# FAT44_1.net
KiCad netlist of a schematic drawn in Altium Designer
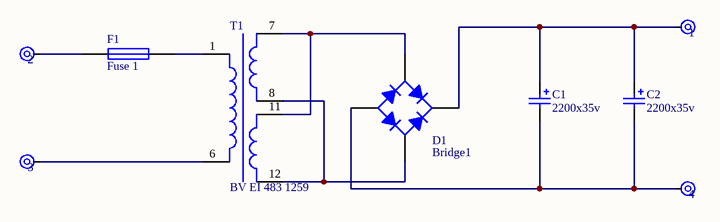
[diagram p0: FAT44_1.SchDoc]

(export (version "E")
  (design (tool "Eeschema 10.0.6"))
  (components
    (comp (ref "1")
      (value "Socket_Ring")
      (footprint "PIN1")
      (description "Socket")
      (fields (field (name "MANUFACTURER") "Generic Components") (field (name "PUBLISHER") "Altium Limited"))
      (libsource (lib "") (part "Socket_Ring_1"))
    )
    (comp (ref "2")
      (value "Socket_Ring")
      (footprint "PIN1")
      (description "Socket")
      (fields (field (name "MANUFACTURER") "Generic Components") (field (name "PUBLISHER") "Altium Limited"))
      (libsource (lib "PAL") (part "Socket_Ring"))
    )
    (comp (ref "3")
      (value "Socket_Ring")
      (footprint "PIN1")
      (description "Socket")
      (fields (field (name "MANUFACTURER") "Generic Components") (field (name "PUBLISHER") "Altium Limited"))
      (libsource (lib "PAL") (part "Socket_Ring"))
    )
    (comp (ref "4")
      (value "Socket_Ring")
      (footprint "PIN1")
      (description "Socket")
      (fields (field (name "MANUFACTURER") "Generic Components") (field (name "PUBLISHER") "Altium Limited"))
      (libsource (lib "") (part "Socket_Ring_1"))
    )
    (comp (ref "C1")
      (value "2200x35v")
      (footprint "el8")
      (description "Polarized Capacitor (Radial)")
      (fields (field (name "MANUFACTURER") "Generic Components") (field (name "PUBLISHER") "Altium Limited"))
      (libsource (lib "BUF") (part "Cap Pol1"))
    )
    (comp (ref "C2")
      (value "2200x35v")
      (footprint "el8")
      (description "Polarized Capacitor (Radial)")
      (fields (field (name "MANUFACTURER") "Generic Components") (field (name "PUBLISHER") "Altium Limited"))
      (libsource (lib "BUF") (part "Cap Pol1"))
    )
    (comp (ref "D1")
      (value "Bridge1")
      (footprint "GSIB2580")
      (description "Full Wave Diode Bridge")
      (fields (field (name "MANUFACTURER") "Generic Components") (field (name "PUBLISHER") "Altium Limited"))
      (libsource (lib "Miscellaneous Devices") (part "Bridge1"))
    )
    (comp (ref "F1")
      (value "Fuse 1")
      (footprint "FUSE3")
      (description "Fuse")
      (fields (field (name "MANUFACTURER") "Generic Components") (field (name "PUBLISHER") "Altium Limited"))
      (libsource (lib "Miscellaneous Devices") (part "Fuse 1"))
    )
    (comp (ref "T1")
      (value "BV EI 483 1259")
      (footprint "BV EI 483 1259_LUT")
      (fields (field (name "MANUFACTURER") "Generic Components") (field (name "PUBLISHER") "Altium Limited"))
      (libsource (lib "PAL") (part "BV EI 483 1259"))
    )
  )
  (nets
    (net (code "1") (name "Net-(2-Pad1)") (class "Default")
      (node (ref "2") (pin "1") (pinfunction "1_1") (pintype "passive"))
      (node (ref "F1") (pin "1") (pinfunction "1_1") (pintype "passive"))
    )
    (net (code "2") (name "Net-(D1-A)") (class "Default")
      (node (ref "4") (pin "1") (pinfunction "1_1") (pintype "passive"))
      (node (ref "C1") (pin "2") (pinfunction "2_2") (pintype "passive"))
      (node (ref "C2") (pin "2") (pinfunction "2_2") (pintype "passive"))
      (node (ref "D1") (pin "1") (pinfunction "A_1") (pintype "passive"))
    )
    (net (code "3") (name "Net-(D1-C-Pad2)") (class "Default")
      (node (ref "D1") (pin "2") (pinfunction "C_2") (pintype "passive"))
      (node (ref "T1") (pin "11") (pinfunction "Sec1+_11") (pintype "passive"))
      (node (ref "T1") (pin "7") (pinfunction "Sec1+_7") (pintype "passive"))
    )
    (net (code "4") (name "Net-(D1-C-Pad4)") (class "Default")
      (node (ref "D1") (pin "4") (pinfunction "C_4") (pintype "passive"))
      (node (ref "T1") (pin "12") (pinfunction "Sec1-_12") (pintype "passive"))
      (node (ref "T1") (pin "8") (pinfunction "Sec1-_8") (pintype "passive"))
    )
    (net (code "5") (name "Net-(D1-K)") (class "Default")
      (node (ref "1") (pin "1") (pinfunction "1_1") (pintype "passive"))
      (node (ref "C1") (pin "1") (pinfunction "1_1") (pintype "passive"))
      (node (ref "C2") (pin "1") (pinfunction "1_1") (pintype "passive"))
      (node (ref "D1") (pin "3") (pinfunction "K_3") (pintype "passive"))
    )
    (net (code "6") (name "Net-(T1-Pri+)") (class "Default")
      (node (ref "F1") (pin "2") (pinfunction "2_2") (pintype "passive"))
      (node (ref "T1") (pin "1") (pinfunction "Pri+_1") (pintype "passive"))
    )
    (net (code "7") (name "Net-(T1-Pri-)") (class "Default")
      (node (ref "3") (pin "1") (pinfunction "1_1") (pintype "passive"))
      (node (ref "T1") (pin "6") (pinfunction "Pri-_6") (pintype "passive"))
    )
  )
)
